# Supply_12V_to_5V-7805_smd.net
KiCad netlist of a schematic drawn in Altium Designer
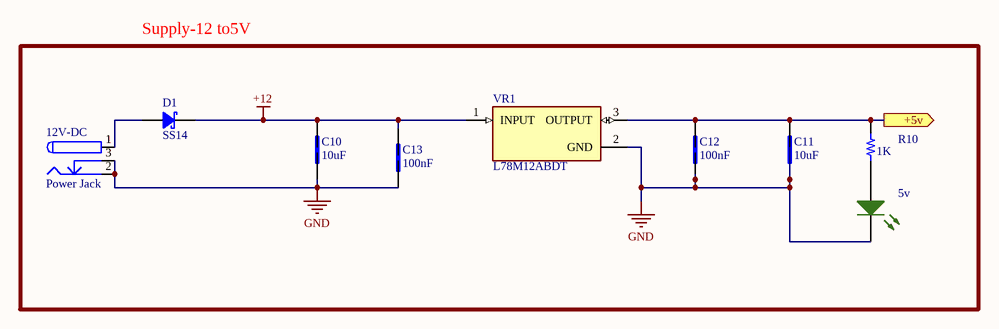
[diagram p0: Supply 12V to 5V-7805 smd.SchDoc]

(export (version "E")
  (design (tool "Eeschema 10.0.6"))
  (components
    (comp (ref "5v")
      (value "LED SMD 0805 GREEN")
      (footprint "LED_0805_GREEN")
      (libsource (lib "Led") (part "LED SMD 0805 GREEN"))
    )
    (comp (ref "12V-DC")
      (value "Power Jack")
      (footprint "DC005")
      (fields (field (name "PARTNUMBER") "DC005-5.5MM"))
      (libsource (lib "Conn Jack") (part "Power Jack"))
    )
    (comp (ref "C10")
      (value "10uF")
      (footprint "CAP 0805_2012")
      (description "COMMERCIAL CHIP STD JAPAN BULK - FN TAPE/REEL, 7 INCH PAPER TAPE-0805")
      (fields (field (name "MP") "LD051C182KAB2A"))
      (libsource (lib "cap 0805") (part "LD051C182KAB2A"))
    )
    (comp (ref "C11")
      (value "10uF")
      (footprint "CAP 0805_2012")
      (description "COMMERCIAL CHIP STD JAPAN BULK - FN TAPE/REEL, 7 INCH PAPER TAPE-0805")
      (fields (field (name "MP") "LD051C182KAB2A"))
      (libsource (lib "cap 0805") (part "LD051C182KAB2A"))
    )
    (comp (ref "C12")
      (value "100nF")
      (footprint "CAP 0805_2012")
      (description "COMMERCIAL CHIP STD JAPAN BULK - FN TAPE/REEL, 7 INCH PAPER TAPE-0805")
      (fields (field (name "MP") "LD051C182KAB2A"))
      (libsource (lib "cap 0805") (part "LD051C182KAB2A"))
    )
    (comp (ref "C13")
      (value "100nF")
      (footprint "CAP 0805_2012")
      (description "COMMERCIAL CHIP STD JAPAN BULK - FN TAPE/REEL, 7 INCH PAPER TAPE-0805")
      (fields (field (name "MP") "LD051C182KAB2A"))
      (libsource (lib "cap 0805") (part "LD051C182KAB2A"))
    )
    (comp (ref "D1")
      (value "SS14")
      (footprint "DO-214AC SMA")
      (description "Diode Schottky 40V 1A Surface Mount SMA (DO-214AC)")
      (libsource (lib "Diode") (part "SS14 (SMD SMA)"))
    )
    (comp (ref "R10")
      (value "1K")
      (footprint "RES 0805_2012")
      (description "SMT Resistor")
      (libsource (lib "Resistor") (part "Res 0805"))
    )
    (comp (ref "VR1")
      (value "L78M12ABDT")
      (footprint "VREG_L78M12ABDT")
      (description "Linear Voltage Regulator IC Positive Fixed 1 Output 500mA DPAK")
      (fields (field (name "MF") "STMicroelectronics"))
      (libsource (lib "L78M12ABDT") (part "L78M12ABDT"))
    )
  )
  (nets
    (net (code "1") (name "+12") (class "Default")
      (node (ref "C10") (pin "2") (pinfunction "2_2") (pintype "passive"))
      (node (ref "C13") (pin "2") (pinfunction "2_2") (pintype "passive"))
      (node (ref "D1") (pin "2") (pinfunction "2_2") (pintype "passive"))
      (node (ref "VR1") (pin "1") (pinfunction "INPUT_1") (pintype "input"))
    )
    (net (code "2") (name "/+5v") (class "Default")
      (node (ref "C11") (pin "2") (pinfunction "2_2") (pintype "passive"))
      (node (ref "C12") (pin "2") (pinfunction "2_2") (pintype "passive"))
      (node (ref "R10") (pin "1") (pinfunction "1_1") (pintype "passive"))
      (node (ref "VR1") (pin "3") (pinfunction "OUTPUT_3") (pintype "bidirectional"))
    )
    (net (code "3") (name "GND") (class "Default")
      (node (ref "12V-DC") (pin "2") (pinfunction "2_2") (pintype "power_in"))
      (node (ref "12V-DC") (pin "3") (pinfunction "3_3") (pintype "power_in"))
      (node (ref "5v") (pin "2") (pinfunction "K_2") (pintype "passive"))
      (node (ref "C10") (pin "1") (pinfunction "1_1") (pintype "passive"))
      (node (ref "C11") (pin "1") (pinfunction "1_1") (pintype "passive"))
      (node (ref "C12") (pin "1") (pinfunction "1_1") (pintype "passive"))
      (node (ref "C13") (pin "1") (pinfunction "1_1") (pintype "passive"))
      (node (ref "VR1") (pin "2") (pinfunction "GND_2") (pintype "power_in"))
    )
    (net (code "4") (name "Net-(5v-A)") (class "Default")
      (node (ref "5v") (pin "1") (pinfunction "A_1") (pintype "passive"))
      (node (ref "R10") (pin "2") (pinfunction "2_2") (pintype "passive"))
    )
    (net (code "5") (name "Net-(12V-DC-Pad1)") (class "Default")
      (node (ref "12V-DC") (pin "1") (pinfunction "1_1") (pintype "power_in"))
      (node (ref "D1") (pin "1") (pinfunction "1_1") (pintype "passive"))
    )
  )
)
